# PlusBit_Sensors.net
KiCad netlist of a schematic drawn in Altium Designer
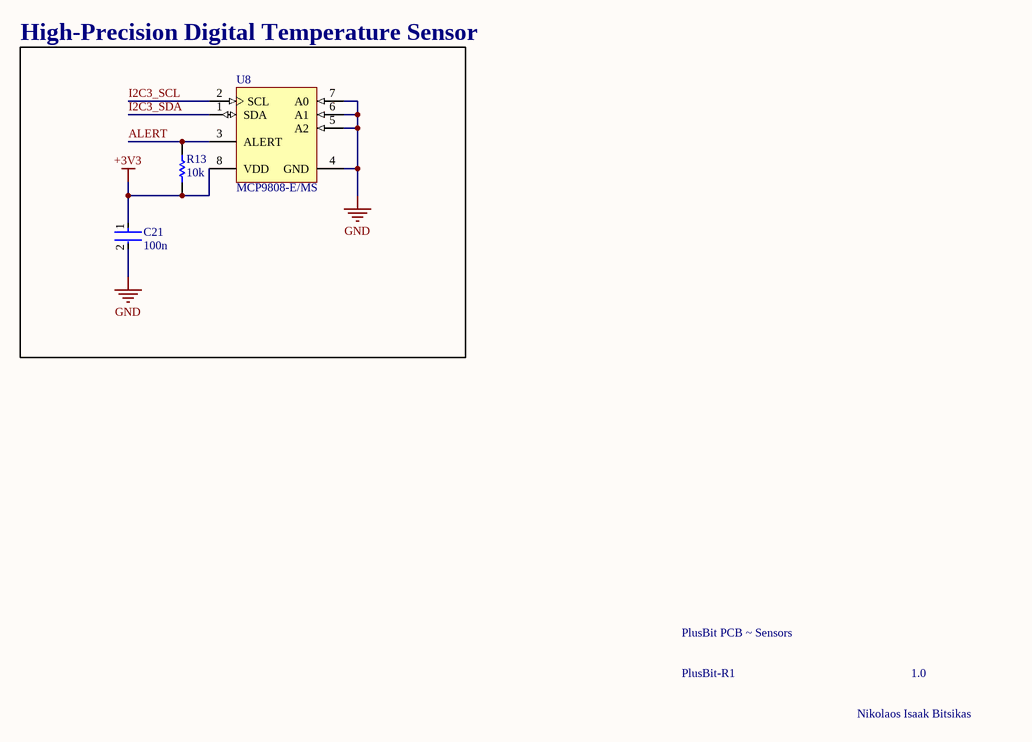
[diagram p0: PlusBit_Sensors.SchDoc]

(export (version "E")
  (design (tool "Eeschema 10.0.6"))
  (components
    (comp (ref "C21")
      (value "100n")
      (footprint "FP-C0402-BB-MFG")
      (description "CAP CER 0.1UF 10V X5R 0402")
      (fields (field (name "MANUFACTURER") "Kemet") (field (name "TOLERANCE") "0.1"))
      (libsource (lib "Altium Content Vault") (part "b4654b650e69147ec39a6b967a45e02"))
    )
    (comp (ref "R13")
      (value "10k")
      (footprint "RESC1608X55X25ML10T15")
      (description "Resistor, 10 KOhm, +/- 5%, 100 mW, -55 to 155 degC, 0603 (1608 Metric), RoHS, Tape and Reel")
      (fields (field (name "MANUFACTURER") "Yageo") (field (name "TOLERANCE") "5%"))
      (libsource (lib "Altium Content Vault") (part "RES-2"))
    )
    (comp (ref "U8")
      (value "MCP9808-E/MS")
      (footprint "MCHP-MSOP-MS8_L")
      (fields (field (name "MANUFACTURER") "Microchip"))
      (libsource (lib "Altium Content Vault") (part "MCHP-MCP9808-MSOP-8"))
    )
  )
  (nets
    (net (code "1") (name "+3V3") (class "Default")
      (node (ref "C21") (pin "1") (pinfunction "1_1") (pintype "passive"))
      (node (ref "R13") (pin "1") (pinfunction "1_1") (pintype "passive"))
      (node (ref "U8") (pin "8") (pinfunction "VDD_8") (pintype "power_in"))
    )
    (net (code "2") (name "/ALERT") (class "Default")
      (node (ref "R13") (pin "2") (pinfunction "2_2") (pintype "passive"))
      (node (ref "U8") (pin "3") (pinfunction "ALERT_3") (pintype "open_collector"))
    )
    (net (code "3") (name "/I2C3_SCL") (class "Default")
      (node (ref "U8") (pin "2") (pinfunction "SCL_2") (pintype "input"))
    )
    (net (code "4") (name "/I2C3_SDA") (class "Default")
      (node (ref "U8") (pin "1") (pinfunction "SDA_1") (pintype "bidirectional"))
    )
    (net (code "5") (name "GND") (class "Default")
      (node (ref "C21") (pin "2") (pinfunction "2_2") (pintype "passive"))
      (node (ref "U8") (pin "4") (pinfunction "GND_4") (pintype "power_in"))
      (node (ref "U8") (pin "5") (pinfunction "A2_5") (pintype "input"))
      (node (ref "U8") (pin "6") (pinfunction "A1_6") (pintype "input"))
      (node (ref "U8") (pin "7") (pinfunction "A0_7") (pintype "input"))
    )
  )
)
